# CP2102N_USB-to-UART_Bridge_V3_0.net
KiCad netlist of a schematic drawn in Altium Designer
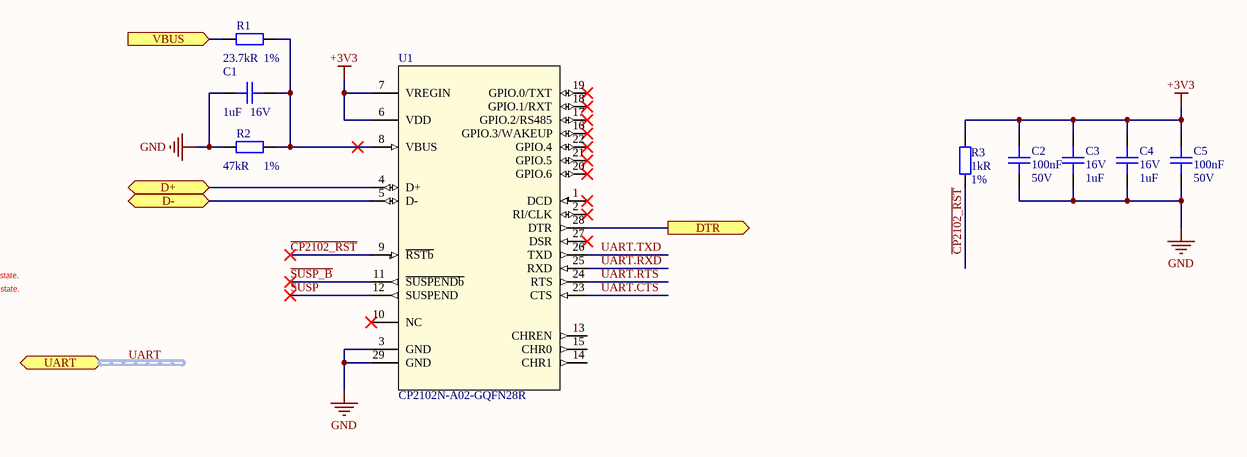
[diagram p0: CP2102N_USB-to-UART_Bridge_V3.0.SchDoc]

(export (version "E")
  (design (tool "Eeschema 10.0.6"))
  (components
    (comp (ref "C1")
      (value "CAP CER 1UF 16V X5R 0402")
      (footprint "C0402")
      (description "1µF ±10% 16V Ceramic Capacitor X5R 0402 (1005 Metric)")
      (fields
        (field (name "MANUFACTURER PART NUMBER") "CC0402KRX5R7BB105")
        (field (name "MANUFACTURER") "Yageo")
        (field (name "VOLTAGE RATING") "16V")
        (field (name "CAPACITANCE") "1uF")
      )
      (libsource (lib "capacitors_smd") (part "CAP CER 1UF 16V X5R 0402"))
    )
    (comp (ref "C2")
      (value "CAP CER 0.1UF 50V X7R 0402")
      (footprint "C0402")
      (description "0.1µF ±10% 50V Ceramic Capacitor X7R 0402 (1005 Metric)")
      (fields
        (field (name "MANUFACTURER PART NUMBER") "CGA2B3X7R1H104K050BB")
        (field (name "MANUFACTURER") "TDK")
        (field (name "CAPACITANCE") "100nF")
        (field (name "VOLTAGE") "50V")
      )
      (libsource (lib "capacitors_smd") (part "CAP CER 0.1UF 50V X7R 0402"))
    )
    (comp (ref "C3")
      (value "CAP CER 1UF 16V X5R 0402")
      (footprint "C0402")
      (description "1µF ±10% 16V Ceramic Capacitor X5R 0402 (1005 Metric)")
      (fields
        (field (name "MANUFACTURER") "Yageo")
        (field (name "MANUFACTURER PART NUMBER") "CC0402KRX5R7BB105")
        (field (name "VOLTAGE RATING") "16V")
        (field (name "CAPACITANCE") "1uF")
      )
      (libsource (lib "capacitors_smd") (part "CAP CER 1UF 16V X5R 0402"))
    )
    (comp (ref "C4")
      (value "CAP CER 1UF 16V X5R 0402")
      (footprint "C0402")
      (description "1µF ±10% 16V Ceramic Capacitor X5R 0402 (1005 Metric)")
      (fields
        (field (name "MANUFACTURER") "Yageo")
        (field (name "MANUFACTURER PART NUMBER") "CC0402KRX5R7BB105")
        (field (name "VOLTAGE RATING") "16V")
        (field (name "CAPACITANCE") "1uF")
      )
      (libsource (lib "capacitors_smd") (part "CAP CER 1UF 16V X5R 0402"))
    )
    (comp (ref "C5")
      (value "CAP CER 0.1UF 50V X7R 0402")
      (footprint "C0402")
      (description "0.1µF ±10% 50V Ceramic Capacitor X7R 0402 (1005 Metric)")
      (fields
        (field (name "MANUFACTURER PART NUMBER") "CGA2B3X7R1H104K050BB")
        (field (name "MANUFACTURER") "TDK")
        (field (name "CAPACITANCE") "100nF")
        (field (name "VOLTAGE") "50V")
      )
      (libsource (lib "capacitors_smd") (part "CAP CER 0.1UF 50V X7R 0402"))
    )
    (comp (ref "R1")
      (value "RES SMD 23.7K OHM 1% 1/16W 0402")
      (footprint "R0402")
      (description "23.7 kOhms ±1% 0.063W, 1/16W Chip Resistor 0402 (1005 Metric) Moisture Resistant Thick Film")
      (fields
        (field (name "MANUFACTURER") "Yageo")
        (field (name "MANUFACTURER PART NUMBER") "RC0402FR-0723K7L")
        (field (name "RESISTANCE") "23.7kR")
        (field (name "TOLERANCE") "1%")
      )
      (libsource (lib "resistors_smd") (part "RES SMD 23.7K OHM 1% 1/16W 0402"))
    )
    (comp (ref "R2")
      (value "RES SMD 47K OHM 1% 1/16W 0402")
      (footprint "R0402")
      (description "47 kOhms ±1% 0.063W, 1/16W Chip Resistor 0402 (1005 Metric) Moisture Resistant Thick Film")
      (fields
        (field (name "MANUFACTURER PART NUMBER") "RC0402FR-0747KL")
        (field (name "MANUFACTURER") "Yageo")
        (field (name "RESISTANCE") "47kR")
        (field (name "TOLERANCE") "1%")
      )
      (libsource (lib "resistors_smd") (part "RES SMD 47K OHM 1% 1/16W 0402"))
    )
    (comp (ref "R3")
      (value "RES SMD 1K OHM 1% 1/16W 0402")
      (footprint "R0402")
      (description "1 kOhms ±1% 0.063W, 1/16W Chip Resistor 0402 (1005 Metric) Moisture Resistant Thick Film")
      (fields
        (field (name "MANUFACTURER PART NUMBER") "RC0402FR-071KL")
        (field (name "MANUFACTURER") "Yageo")
        (field (name "RESISTANCE") "1kR")
        (field (name "TOLERANCE") "1%")
      )
      (libsource (lib "resistors_smd") (part "RES SMD 1K OHM 1% 1/16W 0402"))
    )
    (comp (ref "U1")
      (value "CP2102N-A02-GQFN28R")
      (footprint "QFN28_5X5")
      (description "USB Bridge, USB to UART USB 2.0 UART Interface 28-QFN (5x5)")
      (fields (field (name "MANUFACTURER") "Silicon Labs"))
      (libsource (lib "BLDC_Moto_Driver") (part "IC CP2102N USB TO UART BRIDGE QFN28"))
    )
  )
  (nets
    (net (code "2") (name "+3V3") (class "Default")
      (node (ref "C2") (pin "2") (pinfunction "2_2") (pintype "passive"))
      (node (ref "C3") (pin "2") (pinfunction "2_2") (pintype "passive"))
      (node (ref "C4") (pin "2") (pinfunction "2_2") (pintype "passive"))
      (node (ref "C5") (pin "2") (pinfunction "2_2") (pintype "passive"))
      (node (ref "R3") (pin "1") (pinfunction "1_1") (pintype "passive"))
      (node (ref "U1") (pin "6") (pinfunction "VDD_6") (pintype "power_in"))
      (node (ref "U1") (pin "7") (pinfunction "VREGIN_7") (pintype "power_in"))
    )
    (net (code "3") (name "/CP2102_RST") (class "Default")
      (node (ref "R3") (pin "2") (pinfunction "2_2") (pintype "passive"))
      (node (ref "U1") (pin "9") (pinfunction "RSTb_9") (pintype "input"))
    )
    (net (code "4") (name "/D+") (class "Default")
      (node (ref "U1") (pin "4") (pinfunction "D+_4") (pintype "bidirectional"))
    )
    (net (code "5") (name "/D-") (class "Default")
      (node (ref "U1") (pin "5") (pinfunction "D-_5") (pintype "bidirectional"))
    )
    (net (code "6") (name "/DTR") (class "Default")
      (node (ref "U1") (pin "28") (pinfunction "DTR_28") (pintype "output"))
    )
    (net (code "7") (name "/SUSP") (class "Default")
      (node (ref "U1") (pin "12") (pinfunction "SUSPEND_12") (pintype "output+no_connect"))
    )
    (net (code "8") (name "/SUSP_B") (class "Default")
      (node (ref "U1") (pin "11") (pinfunction "SUSPENDb_11") (pintype "output+no_connect"))
    )
    (net (code "9") (name "/UART.CTS") (class "Default")
      (node (ref "U1") (pin "23") (pinfunction "CTS_23") (pintype "input"))
    )
    (net (code "10") (name "/UART.RTS") (class "Default")
      (node (ref "U1") (pin "24") (pinfunction "RTS_24") (pintype "output"))
    )
    (net (code "11") (name "/UART.RXD") (class "Default")
      (node (ref "U1") (pin "25") (pinfunction "RXD_25") (pintype "input"))
    )
    (net (code "12") (name "/UART.TXD") (class "Default")
      (node (ref "U1") (pin "26") (pinfunction "TXD_26") (pintype "output"))
    )
    (net (code "13") (name "/VBUS") (class "Default")
      (node (ref "R1") (pin "2") (pinfunction "2_2") (pintype "passive"))
    )
    (net (code "15") (name "GND") (class "Default")
      (node (ref "C1") (pin "1") (pinfunction "1_1") (pintype "passive"))
      (node (ref "C2") (pin "1") (pinfunction "1_1") (pintype "passive"))
      (node (ref "C3") (pin "1") (pinfunction "1_1") (pintype "passive"))
      (node (ref "C4") (pin "1") (pinfunction "1_1") (pintype "passive"))
      (node (ref "C5") (pin "1") (pinfunction "1_1") (pintype "passive"))
      (node (ref "R2") (pin "2") (pinfunction "2_2") (pintype "passive"))
      (node (ref "U1") (pin "29") (pinfunction "GND_29") (pintype "power_in"))
      (node (ref "U1") (pin "3") (pinfunction "GND_3") (pintype "power_in"))
    )
    (net (code "16") (name "Net-(U1-VBUS)") (class "Default")
      (node (ref "C1") (pin "2") (pinfunction "2_2") (pintype "passive"))
      (node (ref "R1") (pin "1") (pinfunction "1_1") (pintype "passive"))
      (node (ref "R2") (pin "1") (pinfunction "1_1") (pintype "passive"))
      (node (ref "U1") (pin "8") (pinfunction "VBUS_8") (pintype "input"))
    )
    (net (code "17") (name "unconnected-(U1-CHR0-Pad15)") (class "Default")
      (node (ref "U1") (pin "15") (pinfunction "CHR0_15") (pintype "output"))
    )
    (net (code "18") (name "unconnected-(U1-CHR1-Pad14)") (class "Default")
      (node (ref "U1") (pin "14") (pinfunction "CHR1_14") (pintype "output"))
    )
    (net (code "19") (name "unconnected-(U1-CHREN-Pad13)") (class "Default")
      (node (ref "U1") (pin "13") (pinfunction "CHREN_13") (pintype "output"))
    )
    (net (code "20") (name "unconnected-(U1-DCD-Pad1)") (class "Default")
      (node (ref "U1") (pin "1") (pinfunction "DCD_1") (pintype "input+no_connect"))
    )
    (net (code "21") (name "unconnected-(U1-DSR-Pad27)") (class "Default")
      (node (ref "U1") (pin "27") (pinfunction "DSR_27") (pintype "input+no_connect"))
    )
    (net (code "22") (name "unconnected-(U1-GPIO.0{slash}TXT-Pad19)") (class "Default")
      (node (ref "U1") (pin "19") (pinfunction "GPIO.0/TXT_19") (pintype "bidirectional+no_connect"))
    )
    (net (code "23") (name "unconnected-(U1-GPIO.1{slash}RXT-Pad18)") (class "Default")
      (node (ref "U1") (pin "18") (pinfunction "GPIO.1/RXT_18") (pintype "bidirectional+no_connect"))
    )
    (net (code "24") (name "unconnected-(U1-GPIO.2{slash}RS485-Pad17)") (class "Default")
      (node (ref "U1") (pin "17") (pinfunction "GPIO.2/RS485_17") (pintype "bidirectional+no_connect"))
    )
    (net (code "25") (name "unconnected-(U1-GPIO.3{slash}WAKEUP-Pad16)") (class "Default")
      (node (ref "U1") (pin "16") (pinfunction "GPIO.3/WAKEUP_16") (pintype "bidirectional+no_connect"))
    )
    (net (code "26") (name "unconnected-(U1-GPIO.4-Pad22)") (class "Default")
      (node (ref "U1") (pin "22") (pinfunction "GPIO.4_22") (pintype "bidirectional+no_connect"))
    )
    (net (code "27") (name "unconnected-(U1-GPIO.5-Pad21)") (class "Default")
      (node (ref "U1") (pin "21") (pinfunction "GPIO.5_21") (pintype "bidirectional+no_connect"))
    )
    (net (code "28") (name "unconnected-(U1-GPIO.6-Pad20)") (class "Default")
      (node (ref "U1") (pin "20") (pinfunction "GPIO.6_20") (pintype "bidirectional+no_connect"))
    )
    (net (code "29") (name "unconnected-(U1-NC-Pad10)") (class "Default")
      (node (ref "U1") (pin "10") (pinfunction "NC_10") (pintype "passive+no_connect"))
    )
    (net (code "30") (name "unconnected-(U1-RI{slash}CLK-Pad2)") (class "Default")
      (node (ref "U1") (pin "2") (pinfunction "RI/CLK_2") (pintype "bidirectional+no_connect"))
    )
  )
)
